# Power.net
KiCad netlist of a schematic drawn in Altium Designer
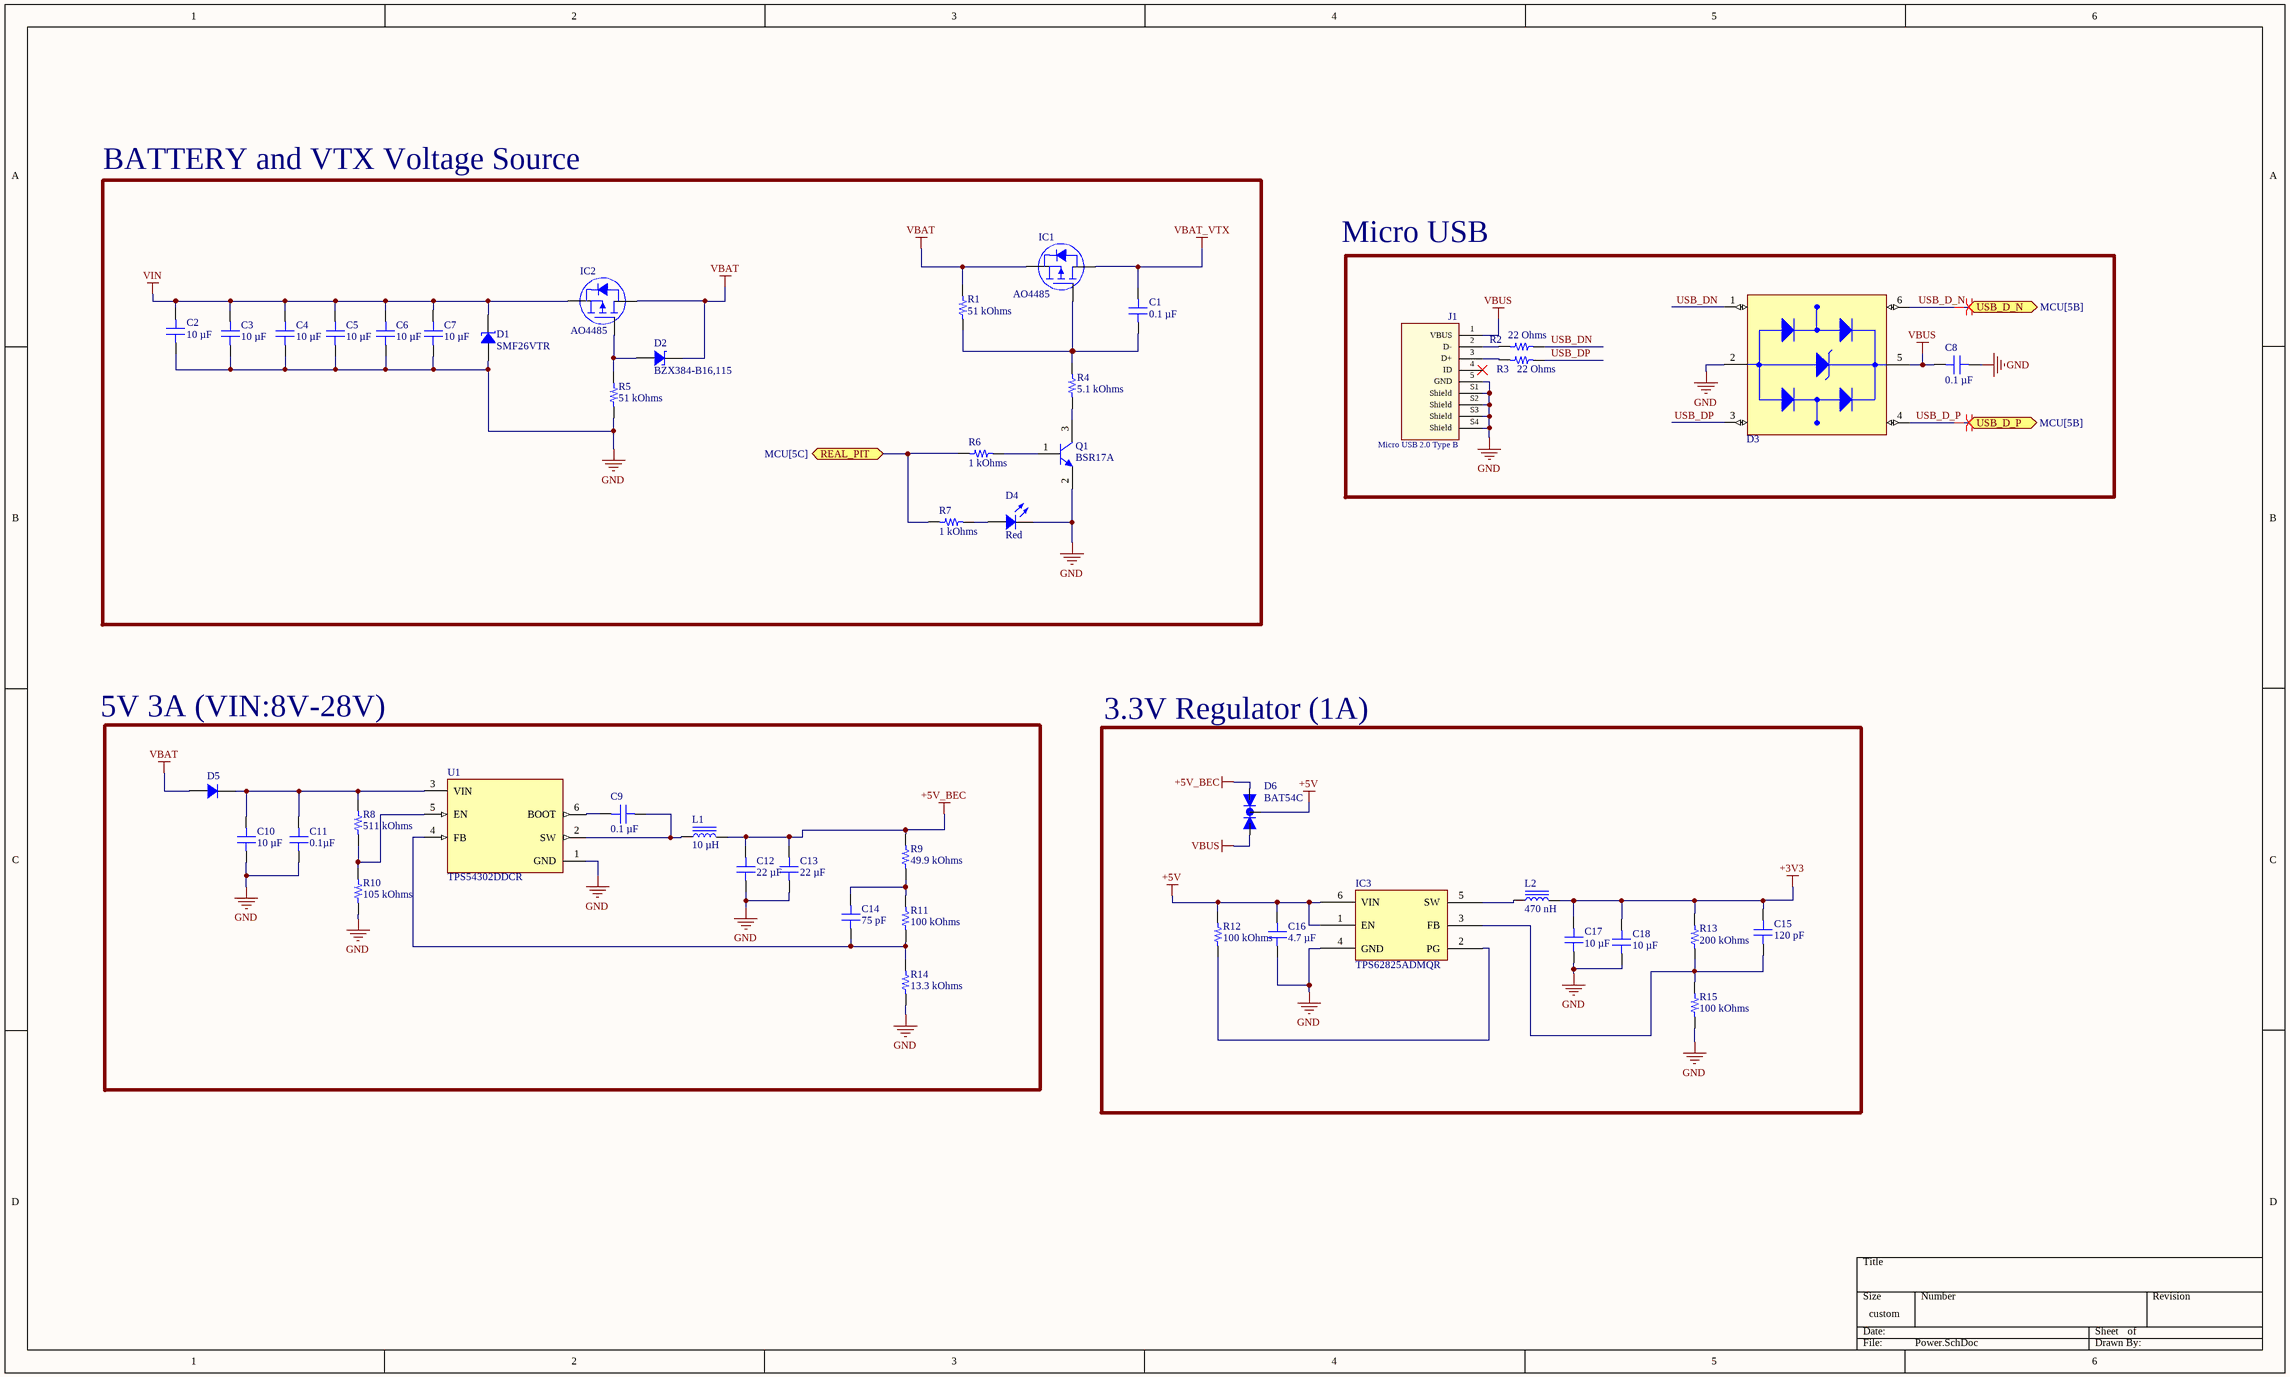
[diagram p0: Power.SchDoc]

(export (version "E")
  (design (tool "Eeschema 10.0.6"))
  (components
    (comp (ref "C1")
      (value "0.1 µF")
      (footprint "CAP 0603_1608")
      (description "CAP CER 0.1UF 50V X7R 0603")
      (fields
        (field (name "PART NUMBER") "CL10B104KB8NNNC")
        (field (name "CAPACITANCE") "0.1 µF")
        (field (name "MANUFACTURER") "Samsung Electro-Mechanics")
      )
      (libsource (lib "Celestial Altium Library - altium_library") (part "Capacitor"))
    )
    (comp (ref "C2")
      (value "10 µF")
      (footprint "MURATA CAP GRM31C 1206_3216")
      (description "CAP CER 10UF 50V X7T 1206")
      (fields
        (field (name "PART NUMBER") "GRM31CD71H106KE11L")
        (field (name "CAPACITANCE") "10 µF")
        (field (name "MANUFACTURER") "Murata Electronics")
      )
      (libsource (lib "Celestial Altium Library - altium_library") (part "Capacitor"))
    )
    (comp (ref "C3")
      (value "10 µF")
      (footprint "MURATA CAP GRM31C 1206_3216")
      (description "CAP CER 10UF 50V X7T 1206")
      (fields
        (field (name "PART NUMBER") "GRM31CD71H106KE11L")
        (field (name "CAPACITANCE") "10 µF")
        (field (name "MANUFACTURER") "Murata Electronics")
      )
      (libsource (lib "Celestial Altium Library - altium_library") (part "Capacitor"))
    )
    (comp (ref "C4")
      (value "10 µF")
      (footprint "MURATA CAP GRM31C 1206_3216")
      (description "CAP CER 10UF 50V X7T 1206")
      (fields
        (field (name "PART NUMBER") "GRM31CD71H106KE11L")
        (field (name "CAPACITANCE") "10 µF")
        (field (name "MANUFACTURER") "Murata Electronics")
      )
      (libsource (lib "Celestial Altium Library - altium_library") (part "Capacitor"))
    )
    (comp (ref "C5")
      (value "10 µF")
      (footprint "MURATA CAP GRM31C 1206_3216")
      (description "CAP CER 10UF 50V X7T 1206")
      (fields
        (field (name "PART NUMBER") "GRM31CD71H106KE11L")
        (field (name "CAPACITANCE") "10 µF")
        (field (name "MANUFACTURER") "Murata Electronics")
      )
      (libsource (lib "Celestial Altium Library - altium_library") (part "Capacitor"))
    )
    (comp (ref "C6")
      (value "10 µF")
      (footprint "MURATA CAP GRM31C 1206_3216")
      (description "CAP CER 10UF 50V X7T 1206")
      (fields
        (field (name "PART NUMBER") "GRM31CD71H106KE11L")
        (field (name "CAPACITANCE") "10 µF")
        (field (name "MANUFACTURER") "Murata Electronics")
      )
      (libsource (lib "Celestial Altium Library - altium_library") (part "Capacitor"))
    )
    (comp (ref "C7")
      (value "10 µF")
      (footprint "MURATA CAP GRM31C 1206_3216")
      (description "CAP CER 10UF 50V X7T 1206")
      (fields
        (field (name "PART NUMBER") "GRM31CD71H106KE11L")
        (field (name "CAPACITANCE") "10 µF")
        (field (name "MANUFACTURER") "Murata Electronics")
      )
      (libsource (lib "Celestial Altium Library - altium_library") (part "Capacitor"))
    )
    (comp (ref "C8")
      (value "0.1 µF")
      (footprint "CAP 0402_1005")
      (description "CAP CER 0.1UF 6.3V X5R 0402")
      (fields
        (field (name "PART NUMBER") "CC0402MRX5R5BB104")
        (field (name "CAPACITANCE") "0.1 µF")
        (field (name "MANUFACTURER") "Yageo")
      )
      (libsource (lib "Celestial Altium Library - altium_library") (part "Capacitor"))
    )
    (comp (ref "C9")
      (value "0.1 µF")
      (footprint "CAP 0402_1005")
      (description "CAP CER 0.1UF 50V X7R 0402")
      (fields
        (field (name "PART NUMBER") "0402B104M500CT")
        (field (name "CAPACITANCE") "0.1 µF")
        (field (name "MANUFACTURER") "Walsin Technology Corporation")
      )
      (libsource (lib "Celestial Altium Library - altium_library") (part "Capacitor"))
    )
    (comp (ref "C10")
      (value "10 µF")
      (footprint "MURATA CAP GRM31C 1206_3216")
      (description "CAP CER 10UF 50V X7T 1206")
      (fields
        (field (name "PART NUMBER") "GRM31CD71H106KE11L")
        (field (name "CAPACITANCE") "10 µF")
        (field (name "MANUFACTURER") "Murata Electronics")
      )
      (libsource (lib "Celestial Altium Library - altium_library") (part "Capacitor"))
    )
    (comp (ref "C11")
      (value "0.1µF")
      (footprint "CAP 0603_1608")
      (description "CAP CER 0.1UF 50V X7R 0603")
      (fields
        (field (name "PART NUMBER") "06035C104JAT2A")
        (field (name "CAPACITANCE") "0.1µF")
        (field (name "MANUFACTURER") "AVX Corporation")
      )
      (libsource (lib "Celestial Altium Library - altium_library") (part "Capacitor"))
    )
    (comp (ref "C12")
      (value "22 µF")
      (footprint "CAP 0402_1005")
      (description "CAP CER 22UF 10V X5R 0402")
      (fields
        (field (name "PART NUMBER") "GRM158R61A226ME15D")
        (field (name "CAPACITANCE") "22 µF")
        (field (name "MANUFACTURER") "Murata Electronics")
      )
      (libsource (lib "Celestial Altium Library - altium_library") (part "Capacitor"))
    )
    (comp (ref "C13")
      (value "22 µF")
      (footprint "CAP 0402_1005")
      (description "CAP CER 22UF 10V X5R 0402")
      (fields
        (field (name "PART NUMBER") "GRM158R61A226ME15D")
        (field (name "CAPACITANCE") "22 µF")
        (field (name "MANUFACTURER") "Murata Electronics")
      )
      (libsource (lib "Celestial Altium Library - altium_library") (part "Capacitor"))
    )
    (comp (ref "C14")
      (value "75 pF")
      (footprint "CAP 0603_1608")
      (description "CAP CER 75PF 50V C0G/NP0 0603")
      (fields
        (field (name "PART NUMBER") "CBR06C750F5GAC")
        (field (name "CAPACITANCE") "75 pF")
        (field (name "MANUFACTURER") "KEMET")
      )
      (libsource (lib "Celestial Altium Library - altium_library") (part "Capacitor"))
    )
    (comp (ref "C15")
      (value "120 pF")
      (footprint "CAP 0402_1005")
      (description "CAP CER 120PF 50V C0G/NP0 0402")
      (fields
        (field (name "PART NUMBER") "C0402C121J5GACAUTO")
        (field (name "CAPACITANCE") "120 pF")
        (field (name "MANUFACTURER") "KEMET")
      )
      (libsource (lib "Celestial Altium Library - altium_library") (part "Capacitor"))
    )
    (comp (ref "C16")
      (value "4.7 µF")
      (footprint "CAP 0603_1608")
      (description "CAP CER 4.7UF 6.3V X5R 0603")
      (fields
        (field (name "PART NUMBER") "JMK107BJ475MK-T")
        (field (name "CAPACITANCE") "4.7 µF")
        (field (name "MANUFACTURER") "Taiyo Yuden")
      )
      (libsource (lib "Celestial Altium Library - altium_library") (part "Capacitor"))
    )
    (comp (ref "C17")
      (value "10 µF")
      (footprint "MURATA GRM188 0603_1608")
      (description "CAP CER 10UF 10V X7R 0603")
      (fields
        (field (name "PART NUMBER") "GRM188Z71A106KA73D")
        (field (name "CAPACITANCE") "10 µF")
        (field (name "MANUFACTURER") "Murata Electronics")
      )
      (libsource (lib "Celestial Altium Library - altium_library") (part "Capacitor"))
    )
    (comp (ref "C18")
      (value "10 µF")
      (footprint "MURATA GRM188 0603_1608")
      (description "CAP CER 10UF 10V X7R 0603")
      (fields
        (field (name "PART NUMBER") "GRM188Z71A106KA73D")
        (field (name "CAPACITANCE") "10 µF")
        (field (name "MANUFACTURER") "Murata Electronics")
      )
      (libsource (lib "Celestial Altium Library - altium_library") (part "Capacitor"))
    )
    (comp (ref "D1")
      (value "SMF26VTR")
      (footprint "SOD123F")
      (description "TVS DIODE 26VWM 42.1VC PMDU")
      (fields (field (name "MANUFACTURER") "Rohm Semiconductor"))
      (libsource (lib "Celestial Altium Library - altium_library") (part "DIODE TVS UNI"))
    )
    (comp (ref "D2")
      (value "BZX384-B16,115")
      (footprint "SOD323")
      (description "DIODE ZENER 16V 300MW SOD323")
      (fields (field (name "MANUFACTURER") "Nexperia USA Inc.") (field (name "TOLERANCE") "±2%"))
      (libsource (lib "Celestial Altium Library - altium_library") (part "Diode Zener"))
    )
    (comp (ref "D3")
      (value "USBLC6-2SC6")
      (footprint "SOT23-6L")
      (description "15V Clamp 6A (8/20µs) Ipp Tvs Diode Surface Mount SOT-23-6")
      (fields (field (name "DESIGNED BY") "İK"))
      (libsource (lib "PCB_Lib") (part "USBLC6-2SC6"))
    )
    (comp (ref "D4")
      (value "Red")
      (footprint "LED 0603_1608 RED")
      (description "LED RED 0603 SMD")
      (fields
        (field (name "PART NUMBER") "B18W1USD-20C000214U1930")
        (field (name "MANUFACTURER") "Harvatek Corporation")
      )
      (libsource (lib "Celestial Altium Library - altium_library") (part "LED"))
    )
    (comp (ref "D5")
      (value "PMEG1030EH,115")
      (footprint "SOD123F")
      (description "DIODE SCHOTTKY 10V 3A SOD123F")
      (fields (field (name "MANUFACTURER") "Nexperia USA Inc."))
      (libsource (lib "Celestial Altium Library - altium_library") (part "Diode"))
    )
    (comp (ref "D6")
      (value "BAT54C")
      (footprint "BAT54C")
      (description "Diode Array 1 Pair Common Cathode 30 V 200mA Surface Mount TO-236-3, SC-59, SOT-23-3")
      (libsource (lib "PCB_Lib") (part "BAT54C"))
    )
    (comp (ref "IC1")
      (value "AO4485")
      (footprint "ALPHAOMEGA SO8 SOP-8L AO4485")
      (description "MOSFET P-CH 40V 10A 8SOIC")
      (fields (field (name "MANUFACTURER") "Alpha & Omega Semiconductor Inc."))
      (libsource (lib "Celestial Altium Library - altium_library") (part "MOSFET P-CH GDS"))
    )
    (comp (ref "IC2")
      (value "AO4485")
      (footprint "ALPHAOMEGA SO8 SOP-8L AO4485")
      (description "MOSFET P-CH 40V 10A 8SOIC")
      (fields (field (name "MANUFACTURER") "Alpha & Omega Semiconductor Inc."))
      (libsource (lib "Celestial Altium Library - altium_library") (part "MOSFET P-CH GDS"))
    )
    (comp (ref "IC3")
      (value "TPS62825ADMQR")
      (footprint "TI - VSON-6 DMQ0006A")
      (description "IC REG BUCK ADJ 2A 6VSON")
      (fields (field (name "MANUFACTURER") "Texas Instruments"))
      (libsource (lib "Celestial Altium Library - altium_library") (part "TI TPS62825ADMQ"))
    )
    (comp (ref "J1")
      (value "Micro USB 2.0 Type B")
      (footprint "629105136821")
      (description "Micro USB 2.0 Type B Horizontal SMT 5 Contacts WR-COM")
      (fields (field (name "PART NUMBER") "629105136821") (field (name "PUBLISHER") "Wurth Elektronik"))
      (libsource (lib "USB") (part "629105136821"))
    )
    (comp (ref "L1")
      (value "10 µH")
      (footprint "WURTH WE-HCI 7050")
      (description "FIXED IND 10UH 3.5A 33 MOHM SMD")
      (fields (field (name "PART NUMBER") "744314101") (field (name "MANUFACTURER") "Würth Elektronik"))
      (libsource (lib "Celestial Altium Library - altium_library") (part "Inductor"))
    )
    (comp (ref "L2")
      (value "470 nH")
      (footprint "IND 0806_2016")
      (description "FIXED IND 470NH 5.2A 25 MOHM SMD")
      (fields
        (field (name "PART NUMBER") "TFM201610ALC-R47MTAA")
        (field (name "MANUFACTURER") "TDK Corporation")
      )
      (libsource (lib "Celestial Altium Library - altium_library") (part "Inductor"))
    )
    (comp (ref "Q1")
      (value "BSR17A")
      (footprint "ON SEMI SOT-23-3")
      (description "TRANS NPN 40V 0.2A SOT-23")
      (fields (field (name "MANUFACTURER") "ON Semiconductor"))
      (libsource (lib "Celestial Altium Library - altium_library") (part "ON SEMI NPN SOT-23-3"))
    )
    (comp (ref "R1")
      (value "51 kOhms")
      (footprint "YAGEO RES 0402_1005")
      (description "RES 51K OHM 5% 1/16W 0402")
      (fields (field (name "PART NUMBER") "RC0402JR-0751KL") (field (name "MANUFACTURER") "Yageo"))
      (libsource (lib "Celestial Altium Library - altium_library") (part "Resistor"))
    )
    (comp (ref "R2")
      (value "22 Ohms")
      (footprint "YAGEO RES 0402_1005")
      (description "RES SMD 22 OHM 5% 1/16W 0402")
      (fields (field (name "PART NUMBER") "AC0402JR-0722RL") (field (name "MANUFACTURER") "Yageo"))
      (libsource (lib "Celestial Altium Library - altium_library") (part "Resistor"))
    )
    (comp (ref "R3")
      (value "22 Ohms")
      (footprint "YAGEO RES 0402_1005")
      (description "RES SMD 22 OHM 5% 1/16W 0402")
      (fields (field (name "PART NUMBER") "AC0402JR-0722RL") (field (name "MANUFACTURER") "Yageo"))
      (libsource (lib "Celestial Altium Library - altium_library") (part "Resistor"))
    )
    (comp (ref "R4")
      (value "5.1 kOhms")
      (footprint "YAGEO RES 0402_1005")
      (description "RES SMD 5.1K OHM 0.1% 1/16W 0402")
      (fields (field (name "PART NUMBER") "RT0402BRE075K1L") (field (name "MANUFACTURER") "Yageo"))
      (libsource (lib "Celestial Altium Library - altium_library") (part "Resistor"))
    )
    (comp (ref "R5")
      (value "51 kOhms")
      (footprint "YAGEO RES 0402_1005")
      (description "RES 51K OHM 5% 1/16W 0402")
      (fields (field (name "PART NUMBER") "RC0402JR-0751KL") (field (name "MANUFACTURER") "Yageo"))
      (libsource (lib "Celestial Altium Library - altium_library") (part "Resistor"))
    )
    (comp (ref "R6")
      (value "1 kOhms")
      (footprint "YAGEO RES 0402_1005")
      (description "RES SMD 1K OHM 0.1% 1/16W 0402")
      (fields (field (name "PART NUMBER") "AT0402BRD071KL") (field (name "MANUFACTURER") "Yageo"))
      (libsource (lib "Celestial Altium Library - altium_library") (part "Resistor"))
    )
    (comp (ref "R7")
      (value "1 kOhms")
      (footprint "YAGEO RES 0402_1005")
      (description "RES SMD 1K OHM 0.1% 1/16W 0402")
      (fields (field (name "PART NUMBER") "AT0402BRD071KL") (field (name "MANUFACTURER") "Yageo"))
      (libsource (lib "Celestial Altium Library - altium_library") (part "Resistor"))
    )
    (comp (ref "R8")
      (value "511 kOhms")
      (footprint "YAGEO RES 0402_1005")
      (description "RES 511K OHM 1% 1/16W 0402")
      (fields (field (name "PART NUMBER") "RC0402FR-07511KL") (field (name "MANUFACTURER") "Yageo"))
      (libsource (lib "Celestial Altium Library - altium_library") (part "Resistor"))
    )
    (comp (ref "R9")
      (value "49.9 kOhms")
      (footprint "YAGEO RES 0201_0603")
      (description "RES 49.9K OHM 1% 1/20W 0201")
      (fields (field (name "PART NUMBER") "RC0201FR-0749K9L") (field (name "MANUFACTURER") "Yageo"))
      (libsource (lib "Celestial Altium Library - altium_library") (part "Resistor"))
    )
    (comp (ref "R10")
      (value "105 kOhms")
      (footprint "YAGEO RES 0402_1005")
      (description "RES 105K OHM 1% 1/16W 0402")
      (fields (field (name "PART NUMBER") "RC0402FR-07105KL") (field (name "MANUFACTURER") "Yageo"))
      (libsource (lib "Celestial Altium Library - altium_library") (part "Resistor"))
    )
    (comp (ref "R11")
      (value "100 kOhms")
      (footprint "YAGEO RES 0402_1005")
      (description "RES 100K OHM 1% 1/16W 0402")
      (fields (field (name "PART NUMBER") "RC0402FR-07100KL") (field (name "MANUFACTURER") "Yageo"))
      (libsource (lib "Celestial Altium Library - altium_library") (part "Resistor"))
    )
    (comp (ref "R12")
      (value "100 kOhms")
      (footprint "YAGEO RES 0402_1005")
      (description "RES 100K OHM 1% 1/16W 0402")
      (fields (field (name "PART NUMBER") "RC0402FR-07100KL") (field (name "MANUFACTURER") "Yageo"))
      (libsource (lib "Celestial Altium Library - altium_library") (part "Resistor"))
    )
    (comp (ref "R13")
      (value "200 kOhms")
      (footprint "YAGEO RES 0402_1005")
      (description "RES 200K OHM 1% 1/16W 0402")
      (fields (field (name "PART NUMBER") "RC0402FR-07200KL") (field (name "MANUFACTURER") "Yageo"))
      (libsource (lib "Celestial Altium Library - altium_library") (part "Resistor"))
    )
    (comp (ref "R14")
      (value "13.3 kOhms")
      (footprint "YAGEO RES 0402_1005")
      (description "RES 13.3K OHM 1% 1/16W 0402")
      (fields (field (name "PART NUMBER") "RC0402FR-0713K3L") (field (name "MANUFACTURER") "Yageo"))
      (libsource (lib "Celestial Altium Library - altium_library") (part "Resistor"))
    )
    (comp (ref "R15")
      (value "100 kOhms")
      (footprint "YAGEO RES 0402_1005")
      (description "RES 100K OHM 1% 1/16W 0402")
      (fields (field (name "PART NUMBER") "RC0402FR-07100KL") (field (name "MANUFACTURER") "Yageo"))
      (libsource (lib "Celestial Altium Library - altium_library") (part "Resistor"))
    )
    (comp (ref "U1")
      (value "TPS54302DDCR")
      (footprint "TPS54302DDCR")
      (description "Buck Switching Regulator IC Positive Adjustable 0.596V 1 Output 3A SOT-23-6 Thin, TSOT-23-6")
      (fields (field (name "MANUFACTURER") "Texas Instrument"))
      (libsource (lib "PCB_Lib") (part "TPS54302DDCR"))
    )
  )
  (nets
    (net (code "1") (name "+3V3") (class "Default")
      (node (ref "C15") (pin "2") (pinfunction "2_2") (pintype "passive"))
      (node (ref "C17") (pin "2") (pinfunction "2_2") (pintype "passive"))
      (node (ref "C18") (pin "2") (pinfunction "2_2") (pintype "passive"))
      (node (ref "L2") (pin "2") (pinfunction "2_2") (pintype "passive"))
      (node (ref "R13") (pin "2") (pinfunction "2_2") (pintype "passive"))
    )
    (net (code "2") (name "+5V") (class "Default")
      (node (ref "C16") (pin "2") (pinfunction "2_2") (pintype "passive"))
      (node (ref "D6") (pin "3") (pinfunction "C_3") (pintype "passive"))
      (node (ref "IC3") (pin "1") (pinfunction "EN_1") (pintype "passive"))
      (node (ref "IC3") (pin "6") (pinfunction "VIN_6") (pintype "passive"))
      (node (ref "R12") (pin "2") (pinfunction "2_2") (pintype "passive"))
    )
    (net (code "3") (name "+5V_BEC") (class "Default")
      (node (ref "C12") (pin "2") (pinfunction "2_2") (pintype "passive"))
      (node (ref "C13") (pin "2") (pinfunction "2_2") (pintype "passive"))
      (node (ref "D6") (pin "1") (pinfunction "A1_1") (pintype "passive"))
      (node (ref "L1") (pin "2") (pinfunction "2_2") (pintype "passive"))
      (node (ref "R9") (pin "2") (pinfunction "2_2") (pintype "passive"))
    )
    (net (code "4") (name "/REAL_PIT") (class "Default")
      (node (ref "R6") (pin "1") (pinfunction "1_1") (pintype "passive"))
      (node (ref "R7") (pin "1") (pinfunction "1_1") (pintype "passive"))
    )
    (net (code "5") (name "/USB_DN") (class "Default")
      (node (ref "D3") (pin "1") (pinfunction "I/O1_IN_1") (pintype "bidirectional"))
      (node (ref "R2") (pin "2") (pinfunction "2_2") (pintype "passive"))
    )
    (net (code "6") (name "/USB_DP") (class "Default")
      (node (ref "D3") (pin "3") (pinfunction "I/O2_IN_3") (pintype "bidirectional"))
      (node (ref "R3") (pin "2") (pinfunction "2_2") (pintype "passive"))
    )
    (net (code "7") (name "/USB_D_N") (class "Default")
      (node (ref "D3") (pin "6") (pinfunction "I/O1_OUT_6") (pintype "bidirectional"))
    )
    (net (code "8") (name "/USB_D_P") (class "Default")
      (node (ref "D3") (pin "4") (pinfunction "I/O2_OUT_4") (pintype "bidirectional"))
    )
    (net (code "9") (name "GND") (class "Default")
      (node (ref "C10") (pin "1") (pinfunction "1_1") (pintype "passive"))
      (node (ref "C11") (pin "1") (pinfunction "1_1") (pintype "passive"))
      (node (ref "C12") (pin "1") (pinfunction "1_1") (pintype "passive"))
      (node (ref "C13") (pin "1") (pinfunction "1_1") (pintype "passive"))
      (node (ref "C16") (pin "1") (pinfunction "1_1") (pintype "passive"))
      (node (ref "C17") (pin "1") (pinfunction "1_1") (pintype "passive"))
      (node (ref "C18") (pin "1") (pinfunction "1_1") (pintype "passive"))
      (node (ref "C2") (pin "1") (pinfunction "1_1") (pintype "passive"))
      (node (ref "C3") (pin "1") (pinfunction "1_1") (pintype "passive"))
      (node (ref "C4") (pin "1") (pinfunction "1_1") (pintype "passive"))
      (node (ref "C5") (pin "1") (pinfunction "1_1") (pintype "passive"))
      (node (ref "C6") (pin "1") (pinfunction "1_1") (pintype "passive"))
      (node (ref "C7") (pin "1") (pinfunction "1_1") (pintype "passive"))
      (node (ref "C8") (pin "1") (pinfunction "1_1") (pintype "passive"))
      (node (ref "D1") (pin "1") (pinfunction "1_1") (pintype "passive"))
      (node (ref "D3") (pin "2") (pinfunction "GND_2") (pintype "power_in"))
      (node (ref "D4") (pin "2") (pinfunction "2_2") (pintype "passive"))
      (node (ref "IC3") (pin "4") (pinfunction "GND_4") (pintype "passive"))
      (node (ref "J1") (pin "5") (pinfunction "GND_5") (pintype "passive"))
      (node (ref "J1") (pin "S1") (pinfunction "Shield_S1") (pintype "passive"))
      (node (ref "J1") (pin "S2") (pinfunction "Shield_S2") (pintype "passive"))
      (node (ref "J1") (pin "S3") (pinfunction "Shield_S3") (pintype "passive"))
      (node (ref "J1") (pin "S4") (pinfunction "Shield_S4") (pintype "passive"))
      (node (ref "Q1") (pin "2") (pinfunction "E_2") (pintype "passive"))
      (node (ref "R10") (pin "1") (pinfunction "1_1") (pintype "passive"))
      (node (ref "R14") (pin "1") (pinfunction "1_1") (pintype "passive"))
      (node (ref "R15") (pin "1") (pinfunction "1_1") (pintype "passive"))
      (node (ref "R5") (pin "1") (pinfunction "1_1") (pintype "passive"))
      (node (ref "U1") (pin "1") (pinfunction "GND_1") (pintype "power_in"))
    )
    (net (code "10") (name "Net-(C1-Pad1)") (class "Default")
      (node (ref "C1") (pin "1") (pinfunction "1_1") (pintype "passive"))
      (node (ref "IC1") (pin "G") (pinfunction "G_G") (pintype "passive"))
      (node (ref "R1") (pin "1") (pinfunction "1_1") (pintype "passive"))
      (node (ref "R4") (pin "2") (pinfunction "2_2") (pintype "passive"))
    )
    (net (code "11") (name "Net-(C14-Pad2)") (class "Default")
      (node (ref "C14") (pin "2") (pinfunction "2_2") (pintype "passive"))
      (node (ref "R11") (pin "2") (pinfunction "2_2") (pintype "passive"))
      (node (ref "R9") (pin "1") (pinfunction "1_1") (pintype "passive"))
    )
    (net (code "12") (name "Net-(D2-Pad1)") (class "Default")
      (node (ref "D2") (pin "1") (pinfunction "1_1") (pintype "passive"))
      (node (ref "IC2") (pin "G") (pinfunction "G_G") (pintype "passive"))
      (node (ref "R5") (pin "2") (pinfunction "2_2") (pintype "passive"))
    )
    (net (code "13") (name "Net-(D4-Pad1)") (class "Default")
      (node (ref "D4") (pin "1") (pinfunction "1_1") (pintype "passive"))
      (node (ref "R7") (pin "2") (pinfunction "2_2") (pintype "passive"))
    )
    (net (code "14") (name "Net-(IC3-FB)") (class "Default")
      (node (ref "C15") (pin "1") (pinfunction "1_1") (pintype "passive"))
      (node (ref "IC3") (pin "3") (pinfunction "FB_3") (pintype "passive"))
      (node (ref "R13") (pin "1") (pinfunction "1_1") (pintype "passive"))
      (node (ref "R15") (pin "2") (pinfunction "2_2") (pintype "passive"))
    )
    (net (code "15") (name "Net-(IC3-PG)") (class "Default")
      (node (ref "IC3") (pin "2") (pinfunction "PG_2") (pintype "passive"))
      (node (ref "R12") (pin "1") (pinfunction "1_1") (pintype "passive"))
    )
    (net (code "16") (name "Net-(IC3-SW)") (class "Default")
      (node (ref "IC3") (pin "5") (pinfunction "SW_5") (pintype "passive"))
      (node (ref "L2") (pin "1") (pinfunction "1_1") (pintype "passive"))
    )
    (net (code "17") (name "Net-(J1-D+)") (class "Default")
      (node (ref "J1") (pin "3") (pinfunction "D+_3") (pintype "passive"))
      (node (ref "R3") (pin "1") (pinfunction "1_1") (pintype "passive"))
    )
    (net (code "18") (name "Net-(J1-D-)") (class "Default")
      (node (ref "J1") (pin "2") (pinfunction "D-_2") (pintype "passive"))
      (node (ref "R2") (pin "1") (pinfunction "1_1") (pintype "passive"))
    )
    (net (code "19") (name "Net-(Q1-B)") (class "Default")
      (node (ref "Q1") (pin "1") (pinfunction "B_1") (pintype "passive"))
      (node (ref "R6") (pin "2") (pinfunction "2_2") (pintype "passive"))
    )
    (net (code "20") (name "Net-(Q1-C)") (class "Default")
      (node (ref "Q1") (pin "3") (pinfunction "C_3") (pintype "passive"))
      (node (ref "R4") (pin "1") (pinfunction "1_1") (pintype "passive"))
    )
    (net (code "21") (name "Net-(U1-BOOT)") (class "Default")
      (node (ref "C9") (pin "1") (pinfunction "1_1") (pintype "passive"))
      (node (ref "U1") (pin "6") (pinfunction "BOOT_6") (pintype "output"))
    )
    (net (code "22") (name "Net-(U1-EN)") (class "Default")
      (node (ref "R10") (pin "2") (pinfunction "2_2") (pintype "passive"))
      (node (ref "R8") (pin "2") (pinfunction "2_2") (pintype "passive"))
      (node (ref "U1") (pin "5") (pinfunction "EN_5") (pintype "input"))
    )
    (net (code "23") (name "Net-(U1-FB)") (class "Default")
      (node (ref "C14") (pin "1") (pinfunction "1_1") (pintype "passive"))
      (node (ref "R11") (pin "1") (pinfunction "1_1") (pintype "passive"))
      (node (ref "R14") (pin "2") (pinfunction "2_2") (pintype "passive"))
      (node (ref "U1") (pin "4") (pinfunction "FB_4") (pintype "input"))
    )
    (net (code "24") (name "Net-(U1-SW)") (class "Default")
      (node (ref "C9") (pin "2") (pinfunction "2_2") (pintype "passive"))
      (node (ref "L1") (pin "1") (pinfunction "1_1") (pintype "passive"))
      (node (ref "U1") (pin "2") (pinfunction "SW_2") (pintype "output"))
    )
    (net (code "25") (name "Net-(U1-VIN)") (class "Default")
      (node (ref "C10") (pin "2") (pinfunction "2_2") (pintype "passive"))
      (node (ref "C11") (pin "2") (pinfunction "2_2") (pintype "passive"))
      (node (ref "D5") (pin "2") (pinfunction "2_2") (pintype "passive"))
      (node (ref "R8") (pin "1") (pinfunction "1_1") (pintype "passive"))
      (node (ref "U1") (pin "3") (pinfunction "VIN_3") (pintype "power_in"))
    )
    (net (code "26") (name "VBAT") (class "Default")
      (node (ref "D2") (pin "2") (pinfunction "2_2") (pintype "passive"))
      (node (ref "D5") (pin "1") (pinfunction "1_1") (pintype "passive"))
      (node (ref "IC1") (pin "S") (pinfunction "S_S") (pintype "passive"))
      (node (ref "IC2") (pin "D") (pinfunction "D_D") (pintype "passive"))
      (node (ref "R1") (pin "2") (pinfunction "2_2") (pintype "passive"))
    )
    (net (code "27") (name "VBAT_VTX") (class "Default")
      (node (ref "C1") (pin "2") (pinfunction "2_2") (pintype "passive"))
      (node (ref "IC1") (pin "D") (pinfunction "D_D") (pintype "passive"))
    )
    (net (code "28") (name "VBUS") (class "Default")
      (node (ref "C8") (pin "2") (pinfunction "2_2") (pintype "passive"))
      (node (ref "D3") (pin "5") (pinfunction "VBUS_5") (pintype "power_in"))
      (node (ref "D6") (pin "2") (pinfunction "A2_2") (pintype "passive"))
      (node (ref "J1") (pin "1") (pinfunction "VBUS_1") (pintype "passive"))
    )
    (net (code "29") (name "VIN") (class "Default")
      (node (ref "C2") (pin "2") (pinfunction "2_2") (pintype "passive"))
      (node (ref "C3") (pin "2") (pinfunction "2_2") (pintype "passive"))
      (node (ref "C4") (pin "2") (pinfunction "2_2") (pintype "passive"))
      (node (ref "C5") (pin "2") (pinfunction "2_2") (pintype "passive"))
      (node (ref "C6") (pin "2") (pinfunction "2_2") (pintype "passive"))
      (node (ref "C7") (pin "2") (pinfunction "2_2") (pintype "passive"))
      (node (ref "D1") (pin "2") (pinfunction "2_2") (pintype "passive"))
      (node (ref "IC2") (pin "S") (pinfunction "S_S") (pintype "passive"))
    )
    (net (code "30") (name "unconnected-(J1-ID-Pad4)") (class "Default")
      (node (ref "J1") (pin "4") (pinfunction "ID_4") (pintype "passive+no_connect"))
    )
  )
)
